# ATtiny841_Basic4.net
KiCad netlist of a schematic drawn in EAGLE
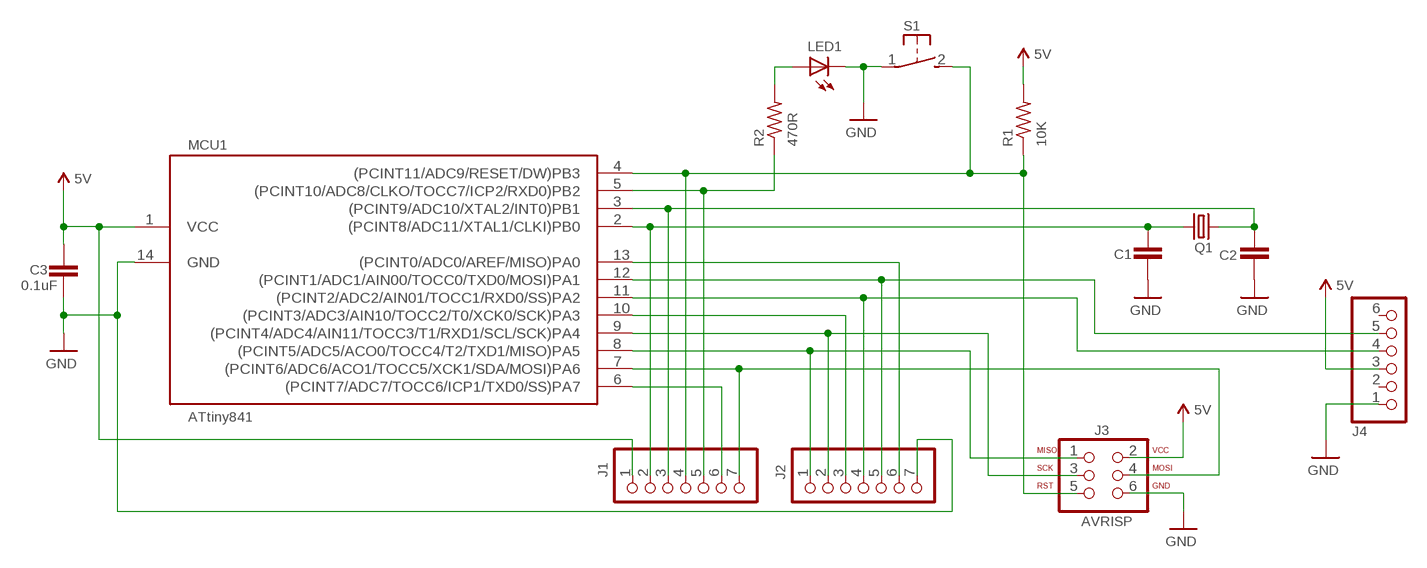
[diagram p0: schematic, sheet 1]

(export (version "E")
  (design (tool "Eeschema 10.0.6"))
  (components
    (comp (ref "C1")
      (value "C-UNPOL")
      (footprint "eagle-import:CAP-PTH-SMALL2")
      (libsource (lib "eagle-import") (part "C-UNPOL"))
    )
    (comp (ref "C2")
      (value "C-UNPOL")
      (footprint "eagle-import:CAP-PTH-SMALL2")
      (libsource (lib "eagle-import") (part "C-UNPOL"))
    )
    (comp (ref "C3")
      (value "0.1uF")
      (footprint "eagle-import:CAP-PTH-SMALL2")
      (libsource (lib "eagle-import") (part "C-UNPOL"))
    )
    (comp (ref "J1")
      (value "PINHD-1X71X07-CLEANBIG")
      (footprint "eagle-import:1X07-CLEANBIG")
      (libsource (lib "eagle-import") (part "PINHD-1X71X07-CLEANBIG"))
    )
    (comp (ref "J2")
      (value "PINHD-1X71X07-CLEANBIG")
      (footprint "eagle-import:1X07-CLEANBIG")
      (libsource (lib "eagle-import") (part "PINHD-1X71X07-CLEANBIG"))
    )
    (comp (ref "J3")
      (value "AVRISP")
      (footprint "eagle-import:2X03-CLEAN")
      (libsource (lib "eagle-import") (part "AVRISP"))
    )
    (comp (ref "J4")
      (value "PINHD-1X6CB")
      (footprint "eagle-import:1X06-CLEANBIG")
      (libsource (lib "eagle-import") (part "PINHD-1X6CB"))
    )
    (comp (ref "LED1")
      (value "LED5MM")
      (footprint "eagle-import:LED5MM")
      (libsource (lib "eagle-import") (part "LED5MM"))
    )
    (comp (ref "MCU1")
      (value "ATtiny841")
      (footprint "eagle-import:SOIC14")
      (libsource (lib "eagle-import") (part "ATTINY441/841-SSU"))
    )
    (comp (ref "Q1")
      (value "CRYSTALHC49S")
      (footprint "eagle-import:HC49_S")
      (libsource (lib "eagle-import") (part "CRYSTALHC49S"))
    )
    (comp (ref "R1")
      (value "10K")
      (footprint "eagle-import:RESISTOR-0207_2V")
      (libsource (lib "eagle-import") (part "RESISTOR-0207/V"))
    )
    (comp (ref "R2")
      (value "470R")
      (footprint "eagle-import:RESISTOR-0207_2V")
      (libsource (lib "eagle-import") (part "RESISTOR-0207/V"))
    )
    (comp (ref "S1")
      (value "SW-SPST-TACT")
      (footprint "eagle-import:DTS-3")
      (libsource (lib "eagle-import") (part "SW-SPST-TACT"))
    )
  )
  (nets
    (net (code "1") (name "5V") (class "Default")
      (node (ref "C3") (pin "1") (pinfunction "1_1") (pintype "passive"))
      (node (ref "J1") (pin "1") (pinfunction "1_1") (pintype "passive"))
      (node (ref "J3") (pin "2") (pinfunction "2_2") (pintype "passive"))
      (node (ref "J4") (pin "3") (pinfunction "3_3") (pintype "passive"))
      (node (ref "MCU1") (pin "1") (pinfunction "VCC_1") (pintype "bidirectional"))
      (node (ref "R1") (pin "2") (pinfunction "2_2") (pintype "passive"))
    )
    (net (code "2") (name "GND") (class "Default")
      (node (ref "C1") (pin "2") (pinfunction "2_2") (pintype "passive"))
      (node (ref "C2") (pin "1") (pinfunction "1_1") (pintype "passive"))
      (node (ref "C3") (pin "2") (pinfunction "2_2") (pintype "passive"))
      (node (ref "J2") (pin "7") (pinfunction "7_7") (pintype "passive"))
      (node (ref "J3") (pin "6") (pinfunction "6_6") (pintype "passive"))
      (node (ref "J4") (pin "1") (pinfunction "1_1") (pintype "passive"))
      (node (ref "LED1") (pin "K") (pinfunction "C_K") (pintype "passive"))
      (node (ref "MCU1") (pin "14") (pinfunction "GND_14") (pintype "bidirectional"))
      (node (ref "S1") (pin "1") (pinfunction "1_1") (pintype "passive"))
    )
    (net (code "3") (name "Net-(LED1-PadA)") (class "Default")
      (node (ref "LED1") (pin "A") (pinfunction "A_A") (pintype "passive"))
      (node (ref "R2") (pin "2") (pinfunction "2_2") (pintype "passive"))
    )
    (net (code "4") (name "Net-(MCU1-(PCINT0{slash}ADC0{slash}AREF{slash}MISO)PA0)") (class "Default")
      (node (ref "J2") (pin "6") (pinfunction "6_6") (pintype "passive"))
      (node (ref "MCU1") (pin "13") (pinfunction "(PCINT0/ADC0/AREF/MISO)PA0_13") (pintype "bidirectional"))
    )
    (net (code "5") (name "Net-(MCU1-(PCINT1{slash}ADC1{slash}AIN00{slash}TOCC0{slash}TXD0{slash}MOSI)PA1)") (class "Default")
      (node (ref "J2") (pin "5") (pinfunction "5_5") (pintype "passive"))
      (node (ref "J4") (pin "5") (pinfunction "5_5") (pintype "passive"))
      (node (ref "MCU1") (pin "12") (pinfunction "(PCINT1/ADC1/AIN00/TOCC0/TXD0/MOSI)PA1_12") (pintype "bidirectional"))
    )
    (net (code "6") (name "Net-(MCU1-(PCINT2{slash}ADC2{slash}AIN01{slash}TOCC1{slash}RXD0{slash}SS)PA2)") (class "Default")
      (node (ref "J2") (pin "4") (pinfunction "4_4") (pintype "passive"))
      (node (ref "J4") (pin "4") (pinfunction "4_4") (pintype "passive"))
      (node (ref "MCU1") (pin "11") (pinfunction "(PCINT2/ADC2/AIN01/TOCC1/RXD0/SS)PA2_11") (pintype "bidirectional"))
    )
    (net (code "7") (name "Net-(MCU1-(PCINT3{slash}ADC3{slash}AIN10{slash}TOCC2{slash}T0{slash}XCK0{slash}SCK)PA3)") (class "Default")
      (node (ref "J2") (pin "3") (pinfunction "3_3") (pintype "passive"))
      (node (ref "MCU1") (pin "10") (pinfunction "(PCINT3/ADC3/AIN10/TOCC2/T0/XCK0/SCK)PA3_10") (pintype "bidirectional"))
    )
    (net (code "8") (name "Net-(MCU1-(PCINT4{slash}ADC4{slash}AIN11{slash}TOCC3{slash}T1{slash}RXD1{slash}SCL{slash}SCK)PA4)") (class "Default")
      (node (ref "J2") (pin "2") (pinfunction "2_2") (pintype "passive"))
      (node (ref "J3") (pin "3") (pinfunction "3_3") (pintype "passive"))
      (node (ref "MCU1") (pin "9") (pinfunction "(PCINT4/ADC4/AIN11/TOCC3/T1/RXD1/SCL/SCK)PA4_9") (pintype "bidirectional"))
    )
    (net (code "9") (name "Net-(MCU1-(PCINT5{slash}ADC5{slash}ACO0{slash}TOCC4{slash}T2{slash}TXD1{slash}MISO)PA5)") (class "Default")
      (node (ref "J2") (pin "1") (pinfunction "1_1") (pintype "passive"))
      (node (ref "J3") (pin "1") (pinfunction "1_1") (pintype "passive"))
      (node (ref "MCU1") (pin "8") (pinfunction "(PCINT5/ADC5/ACO0/TOCC4/T2/TXD1/MISO)PA5_8") (pintype "bidirectional"))
    )
    (net (code "10") (name "Net-(MCU1-(PCINT6{slash}ADC6{slash}ACO1{slash}TOCC5{slash}XCK1{slash}SDA{slash}MOSI)PA6)") (class "Default")
      (node (ref "J1") (pin "7") (pinfunction "7_7") (pintype "passive"))
      (node (ref "J3") (pin "4") (pinfunction "4_4") (pintype "passive"))
      (node (ref "MCU1") (pin "7") (pinfunction "(PCINT6/ADC6/ACO1/TOCC5/XCK1/SDA/MOSI)PA6_7") (pintype "bidirectional"))
    )
    (net (code "11") (name "Net-(MCU1-(PCINT7{slash}ADC7{slash}TOCC6{slash}ICP1{slash}TXD0{slash}SS)PA7)") (class "Default")
      (node (ref "J1") (pin "6") (pinfunction "6_6") (pintype "passive"))
      (node (ref "MCU1") (pin "6") (pinfunction "(PCINT7/ADC7/TOCC6/ICP1/TXD0/SS)PA7_6") (pintype "bidirectional"))
    )
    (net (code "12") (name "Net-(MCU1-(PCINT8{slash}ADC11{slash}XTAL1{slash}CLKI)PB0)") (class "Default")
      (node (ref "C1") (pin "1") (pinfunction "1_1") (pintype "passive"))
      (node (ref "J1") (pin "2") (pinfunction "2_2") (pintype "passive"))
      (node (ref "MCU1") (pin "2") (pinfunction "(PCINT8/ADC11/XTAL1/CLKI)PB0_2") (pintype "bidirectional"))
      (node (ref "Q1") (pin "1") (pinfunction "1_1") (pintype "passive"))
    )
    (net (code "13") (name "Net-(MCU1-(PCINT9{slash}ADC10{slash}XTAL2{slash}INT0)PB1)") (class "Default")
      (node (ref "C2") (pin "2") (pinfunction "2_2") (pintype "passive"))
      (node (ref "J1") (pin "3") (pinfunction "3_3") (pintype "passive"))
      (node (ref "MCU1") (pin "3") (pinfunction "(PCINT9/ADC10/XTAL2/INT0)PB1_3") (pintype "bidirectional"))
      (node (ref "Q1") (pin "2") (pinfunction "2_2") (pintype "passive"))
    )
    (net (code "14") (name "Net-(MCU1-(PCINT10{slash}ADC8{slash}CLKO{slash}TOCC7{slash}ICP2{slash}RXD0)PB2)") (class "Default")
      (node (ref "J1") (pin "5") (pinfunction "5_5") (pintype "passive"))
      (node (ref "MCU1") (pin "5") (pinfunction "(PCINT10/ADC8/CLKO/TOCC7/ICP2/RXD0)PB2_5") (pintype "bidirectional"))
      (node (ref "R2") (pin "1") (pinfunction "1_1") (pintype "passive"))
    )
    (net (code "15") (name "Net-(MCU1-(PCINT11{slash}ADC9{slash}RESET{slash}DW)PB3)") (class "Default")
      (node (ref "J1") (pin "4") (pinfunction "4_4") (pintype "passive"))
      (node (ref "J3") (pin "5") (pinfunction "5_5") (pintype "passive"))
      (node (ref "MCU1") (pin "4") (pinfunction "(PCINT11/ADC9/RESET/DW)PB3_4") (pintype "bidirectional"))
      (node (ref "R1") (pin "1") (pinfunction "1_1") (pintype "passive"))
      (node (ref "S1") (pin "2") (pinfunction "2_2") (pintype "passive"))
    )
    (net (code "16") (name "unconnected-(J4-Pad2)") (class "Default")
      (node (ref "J4") (pin "2") (pinfunction "2_2") (pintype "passive"))
    )
    (net (code "17") (name "unconnected-(J4-Pad6)") (class "Default")
      (node (ref "J4") (pin "6") (pinfunction "6_6") (pintype "passive"))
    )
  )
)
